# USR_IO_IPMI.net
KiCad netlist of a schematic drawn in Altium Designer
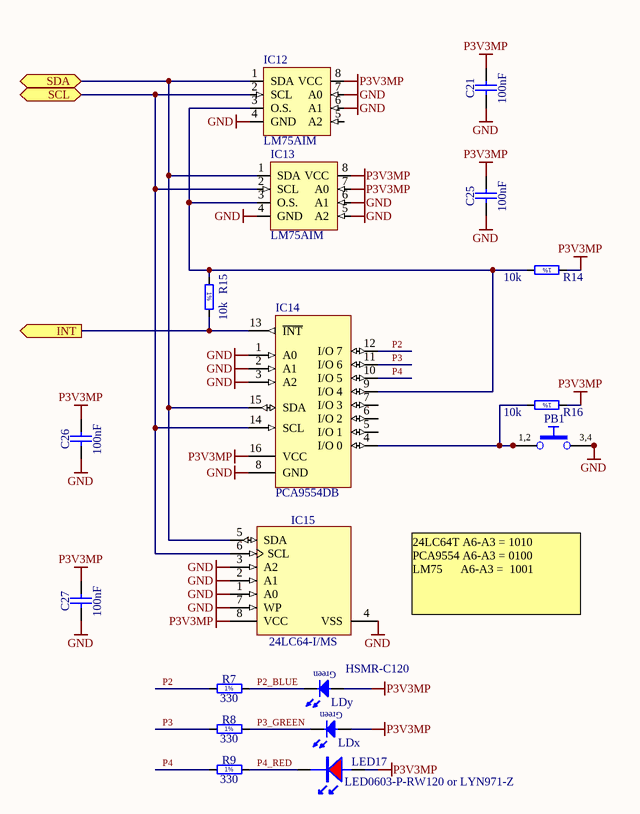
[diagram p0: USR_IO_IPMI.SchDoc]

(export (version "E")
  (design (tool "Eeschema 10.0.6"))
  (components
    (comp (ref "C21")
      (value "100nF")
      (footprint "CAPC1005X55N")
      (description "Non-polarised capacitor")
      (fields
        (field (name "PART NUMBER") "CC0402_100NF_16V_10%_X7R")
        (field (name "VOLTAGE") "16V")
        (field (name "AUTHOR") "CERN DEM JLC")
      )
      (libsource (lib "Capacitors") (part "Capacitor - non polarized"))
    )
    (comp (ref "C25")
      (value "100nF")
      (footprint "CAPC1005X55N")
      (description "Non-polarised capacitor")
      (fields
        (field (name "PART NUMBER") "CC0402_100NF_16V_10%_X7R")
        (field (name "VOLTAGE") "16V")
        (field (name "AUTHOR") "CERN DEM JLC")
      )
      (libsource (lib "Capacitors") (part "Capacitor - non polarized"))
    )
    (comp (ref "C26")
      (value "100nF")
      (footprint "CAPC1005X55N")
      (description "Non-polarised capacitor")
      (fields
        (field (name "PART NUMBER") "CC0402_100NF_16V_10%_X7R")
        (field (name "VOLTAGE") "16V")
        (field (name "AUTHOR") "CERN DEM JLC")
      )
      (libsource (lib "Capacitors") (part "Capacitor - non polarized"))
    )
    (comp (ref "C27")
      (value "100nF")
      (footprint "CAPC1005X55N")
      (description "Non-polarised capacitor")
      (fields
        (field (name "PART NUMBER") "CC0402_100NF_16V_10%_X7R")
        (field (name "VOLTAGE") "16V")
        (field (name "AUTHOR") "CERN DEM JLC")
      )
      (libsource (lib "Capacitors") (part "Capacitor - non polarized"))
    )
    (comp (ref "IC12")
      (value "LM75AIM")
      (footprint "SOIC127P600X175-8N")
      (description "I2C temperature sensor")
      (libsource (lib "LIBRARY_SCH") (part "SENS_LM75"))
    )
    (comp (ref "IC13")
      (value "LM75AIM")
      (footprint "SOIC127P600X175-8N")
      (description "I2C temperature sensor")
      (libsource (lib "LIBRARY_SCH") (part "SENS_LM75"))
    )
    (comp (ref "IC14")
      (value "PCA9554DB")
      (footprint "SOP65P640X120-16N")
      (description "8-bit I2C-bus SMBus I/O port with interrupt")
      (libsource (lib "wr_switch") (part "PCA9554D"))
    )
    (comp (ref "IC15")
      (value "24LC64-I/MS")
      (footprint "SOP65P490X110-8N")
      (description "64K I2C Serial EEPROM")
      (fields (field (name "MANUFACTURER") "MICROCHIP TECHNOLOGY") (field (name "AUTHOR") "CERN DEM JLC"))
      (libsource (lib "ICs And Semiconductors") (part "24LC64-I/MS"))
    )
    (comp (ref "LDx")
      (value "Green")
      (footprint "LED_AVAGO_HSME-C120")
      (description "LED Green 1C 2A")
      (fields
        (field (name "PART NUMBER") "LED_AVAGO_HSME-C120")
        (field (name "MANUFACTURER") "AVAGO TECHNOLOGIES")
        (field (name "AUTHOR") "CERN DEM JMW")
      )
      (libsource (lib "ICs And Semiconductors") (part "LED Green 1C 2A"))
    )
    (comp (ref "LDy")
      (value "HSMR-C120")
      (footprint "LED_AVAGO_HSME-C120")
      (description "LED BLUE")
      (fields (field (name "AUTHOR") "CERN DEM JMW"))
      (libsource (lib "ICs And Semiconductors") (part "LED Green 1C 2A"))
    )
    (comp (ref "LED17")
      (value "LED0603-P-RW120 or LYN971-Z")
      (footprint "led_0603R")
      (description "LED 0603 red")
      (libsource (lib "LIBRARY_SCH") (part "LED_0603R"))
    )
    (comp (ref "PB1")
      (value "Push Button")
      (footprint "SW_C&K_HDT0001")
      (description "Push-Button Switch SPDT")
      (fields
        (field (name "PART NUMBER") "SW_C&K_HDT0001")
        (field (name "MANUFACTURER") "C&K")
        (field (name "AUTHOR") "CERN DEM JLC")
      )
      (libsource (lib "Eletro-mechanical") (part "PB SPST 12NO-34NO"))
    )
    (comp (ref "R7")
      (value "330")
      (footprint "RESC1608X55N")
      (description "Resistor - 1%")
      (fields
        (field (name "PART NUMBER") "R0603_330R_1%_0.1W_100PPM")
        (field (name "POWER") "0.1W")
        (field (name "AUTHOR") "CERN DEM JLC")
      )
      (libsource (lib "Resistors") (part "Resistor - 1%"))
    )
    (comp (ref "R8")
      (value "330")
      (footprint "RESC1608X55N")
      (description "Resistor - 1%")
      (fields
        (field (name "PART NUMBER") "R0603_330R_1%_0.1W_100PPM")
        (field (name "POWER") "0.1W")
        (field (name "AUTHOR") "CERN DEM JLC")
      )
      (libsource (lib "Resistors") (part "Resistor - 1%"))
    )
    (comp (ref "R9")
      (value "330")
      (footprint "RESC1608X55N")
      (description "Resistor - 1%")
      (fields
        (field (name "PART NUMBER") "R0603_330R_1%_0.1W_100PPM")
        (field (name "POWER") "0.1W")
        (field (name "AUTHOR") "CERN DEM JLC")
      )
      (libsource (lib "Resistors") (part "Resistor - 1%"))
    )
    (comp (ref "R14")
      (value "10k")
      (footprint "RESC1005X40N")
      (description "Resistor - 1%")
      (fields
        (field (name "PART NUMBER") "R0402_10K_1%_0.0625W_100PPM")
        (field (name "POWER") "0.0625W")
        (field (name "AUTHOR") "CERN DEM JLC")
      )
      (libsource (lib "Resistors") (part "Resistor - 1%"))
    )
    (comp (ref "R15")
      (value "10k")
      (footprint "RESC1005X40N")
      (description "Resistor - 1%")
      (fields
        (field (name "PART NUMBER") "R0402_10K_1%_0.0625W_100PPM")
        (field (name "POWER") "0.0625W")
        (field (name "AUTHOR") "CERN DEM JLC")
      )
      (libsource (lib "Resistors") (part "Resistor - 1%"))
    )
    (comp (ref "R16")
      (value "10k")
      (footprint "RESC1005X40N")
      (description "Resistor - 1%")
      (fields
        (field (name "PART NUMBER") "R0402_10K_1%_0.0625W_100PPM")
        (field (name "POWER") "0.0625W")
        (field (name "AUTHOR") "CERN DEM JLC")
      )
      (libsource (lib "Resistors") (part "Resistor - 1%"))
    )
  )
  (nets
    (net (code "1") (name "/INT") (class "Default")
      (node (ref "IC14") (pin "13") (pinfunction "~{INT}_13") (pintype "output"))
      (node (ref "R15") (pin "2") (pinfunction "2_2") (pintype "passive"))
    )
    (net (code "2") (name "/P2") (class "Default")
      (node (ref "IC14") (pin "12") (pinfunction "I/O_7_12") (pintype "bidirectional"))
      (node (ref "R7") (pin "1") (pinfunction "1_1") (pintype "passive"))
    )
    (net (code "3") (name "/P2_BLUE") (class "Default")
      (node (ref "LDy") (pin "1") (pinfunction "C_1") (pintype "passive"))
      (node (ref "R7") (pin "2") (pinfunction "2_2") (pintype "passive"))
    )
    (net (code "4") (name "/P3") (class "Default")
      (node (ref "IC14") (pin "11") (pinfunction "I/O_6_11") (pintype "bidirectional"))
      (node (ref "R8") (pin "1") (pinfunction "1_1") (pintype "passive"))
    )
    (net (code "5") (name "/P3_GREEN") (class "Default")
      (node (ref "LDx") (pin "1") (pinfunction "C_1") (pintype "passive"))
      (node (ref "R8") (pin "2") (pinfunction "2_2") (pintype "passive"))
    )
    (net (code "6") (name "/P4") (class "Default")
      (node (ref "IC14") (pin "10") (pinfunction "I/O_5_10") (pintype "bidirectional"))
      (node (ref "R9") (pin "1") (pinfunction "1_1") (pintype "passive"))
    )
    (net (code "7") (name "/P4_RED") (class "Default")
      (node (ref "LED17") (pin "K") (pinfunction "K_K") (pintype "passive"))
      (node (ref "R9") (pin "2") (pinfunction "2_2") (pintype "passive"))
    )
    (net (code "8") (name "/SCL") (class "Default")
      (node (ref "IC12") (pin "2") (pinfunction "SCL_2") (pintype "input"))
      (node (ref "IC13") (pin "2") (pinfunction "SCL_2") (pintype "input"))
      (node (ref "IC14") (pin "14") (pinfunction "SCL_14") (pintype "input"))
      (node (ref "IC15") (pin "6") (pinfunction "SCL_6") (pintype "input"))
    )
    (net (code "9") (name "/SDA") (class "Default")
      (node (ref "IC12") (pin "1") (pinfunction "SDA_1") (pintype "bidirectional"))
      (node (ref "IC13") (pin "1") (pinfunction "SDA_1") (pintype "bidirectional"))
      (node (ref "IC14") (pin "15") (pinfunction "SDA_15") (pintype "bidirectional"))
      (node (ref "IC15") (pin "5") (pinfunction "SDA_5") (pintype "bidirectional"))
    )
    (net (code "10") (name "GND") (class "Default")
      (node (ref "C21") (pin "2") (pinfunction "2_2") (pintype "passive"))
      (node (ref "C25") (pin "2") (pinfunction "2_2") (pintype "passive"))
      (node (ref "C26") (pin "2") (pinfunction "2_2") (pintype "passive"))
      (node (ref "C27") (pin "2") (pinfunction "2_2") (pintype "passive"))
      (node (ref "IC12") (pin "4") (pinfunction "GND_4") (pintype "power_in"))
      (node (ref "IC12") (pin "6") (pinfunction "A1_6") (pintype "input"))
      (node (ref "IC12") (pin "7") (pinfunction "A0_7") (pintype "input"))
      (node (ref "IC13") (pin "4") (pinfunction "GND_4") (pintype "power_in"))
      (node (ref "IC13") (pin "5") (pinfunction "A2_5") (pintype "input"))
      (node (ref "IC13") (pin "6") (pinfunction "A1_6") (pintype "input"))
      (node (ref "IC14") (pin "1") (pinfunction "A0_1") (pintype "input"))
      (node (ref "IC14") (pin "2") (pinfunction "A1_2") (pintype "input"))
      (node (ref "IC14") (pin "3") (pinfunction "A2_3") (pintype "input"))
      (node (ref "IC14") (pin "8") (pinfunction "GND_8") (pintype "power_in"))
      (node (ref "IC15") (pin "1") (pinfunction "A0_1") (pintype "input"))
      (node (ref "IC15") (pin "2") (pinfunction "A1_2") (pintype "input"))
      (node (ref "IC15") (pin "3") (pinfunction "A2_3") (pintype "input"))
      (node (ref "IC15") (pin "4") (pinfunction "VSS_4") (pintype "power_in"))
      (node (ref "IC15") (pin "7") (pinfunction "WP_7") (pintype "input"))
      (node (ref "PB1") (pin "3") (pinfunction "3_3") (pintype "passive"))
      (node (ref "PB1") (pin "4") (pinfunction "4_4") (pintype "passive"))
    )
    (net (code "11") (name "Net-(IC12-O.S.)") (class "Default")
      (node (ref "IC12") (pin "3") (pinfunction "O.S._3") (pintype "open_collector"))
      (node (ref "IC13") (pin "3") (pinfunction "O.S._3") (pintype "open_collector"))
      (node (ref "IC14") (pin "9") (pinfunction "I/O_4_9") (pintype "bidirectional"))
      (node (ref "R14") (pin "2") (pinfunction "2_2") (pintype "passive"))
      (node (ref "R15") (pin "1") (pinfunction "1_1") (pintype "passive"))
    )
    (net (code "12") (name "Net-(IC14-I{slash}O_0)") (class "Default")
      (node (ref "IC14") (pin "4") (pinfunction "I/O_0_4") (pintype "bidirectional"))
      (node (ref "PB1") (pin "1") (pinfunction "1_1") (pintype "passive"))
      (node (ref "PB1") (pin "2") (pinfunction "2_2") (pintype "passive"))
      (node (ref "R16") (pin "2") (pinfunction "2_2") (pintype "passive"))
    )
    (net (code "13") (name "P3V3MP") (class "Default")
      (node (ref "C21") (pin "1") (pinfunction "1_1") (pintype "passive"))
      (node (ref "C25") (pin "1") (pinfunction "1_1") (pintype "passive"))
      (node (ref "C26") (pin "1") (pinfunction "1_1") (pintype "passive"))
      (node (ref "C27") (pin "1") (pinfunction "1_1") (pintype "passive"))
      (node (ref "IC12") (pin "8") (pinfunction "VCC_8") (pintype "power_in"))
      (node (ref "IC13") (pin "7") (pinfunction "A0_7") (pintype "input"))
      (node (ref "IC13") (pin "8") (pinfunction "VCC_8") (pintype "power_in"))
      (node (ref "IC14") (pin "16") (pinfunction "VCC_16") (pintype "power_in"))
      (node (ref "IC15") (pin "8") (pinfunction "VCC_8") (pintype "power_in"))
      (node (ref "LDx") (pin "2") (pinfunction "A_2") (pintype "passive"))
      (node (ref "LDy") (pin "2") (pinfunction "A_2") (pintype "passive"))
      (node (ref "LED17") (pin "A") (pinfunction "A_A") (pintype "passive"))
      (node (ref "R14") (pin "1") (pinfunction "1_1") (pintype "passive"))
      (node (ref "R16") (pin "1") (pinfunction "1_1") (pintype "passive"))
    )
    (net (code "14") (name "unconnected-(IC12-A2-Pad5)") (class "Default")
      (node (ref "IC12") (pin "5") (pinfunction "A2_5") (pintype "input"))
    )
    (net (code "15") (name "unconnected-(IC14-I{slash}O_1-Pad5)") (class "Default")
      (node (ref "IC14") (pin "5") (pinfunction "I/O_1_5") (pintype "bidirectional"))
    )
    (net (code "16") (name "unconnected-(IC14-I{slash}O_2-Pad6)") (class "Default")
      (node (ref "IC14") (pin "6") (pinfunction "I/O_2_6") (pintype "bidirectional"))
    )
    (net (code "17") (name "unconnected-(IC14-I{slash}O_3-Pad7)") (class "Default")
      (node (ref "IC14") (pin "7") (pinfunction "I/O_3_7") (pintype "bidirectional"))
    )
  )
)
